# ioboard.net
KiCad netlist of a schematic drawn in EAGLE
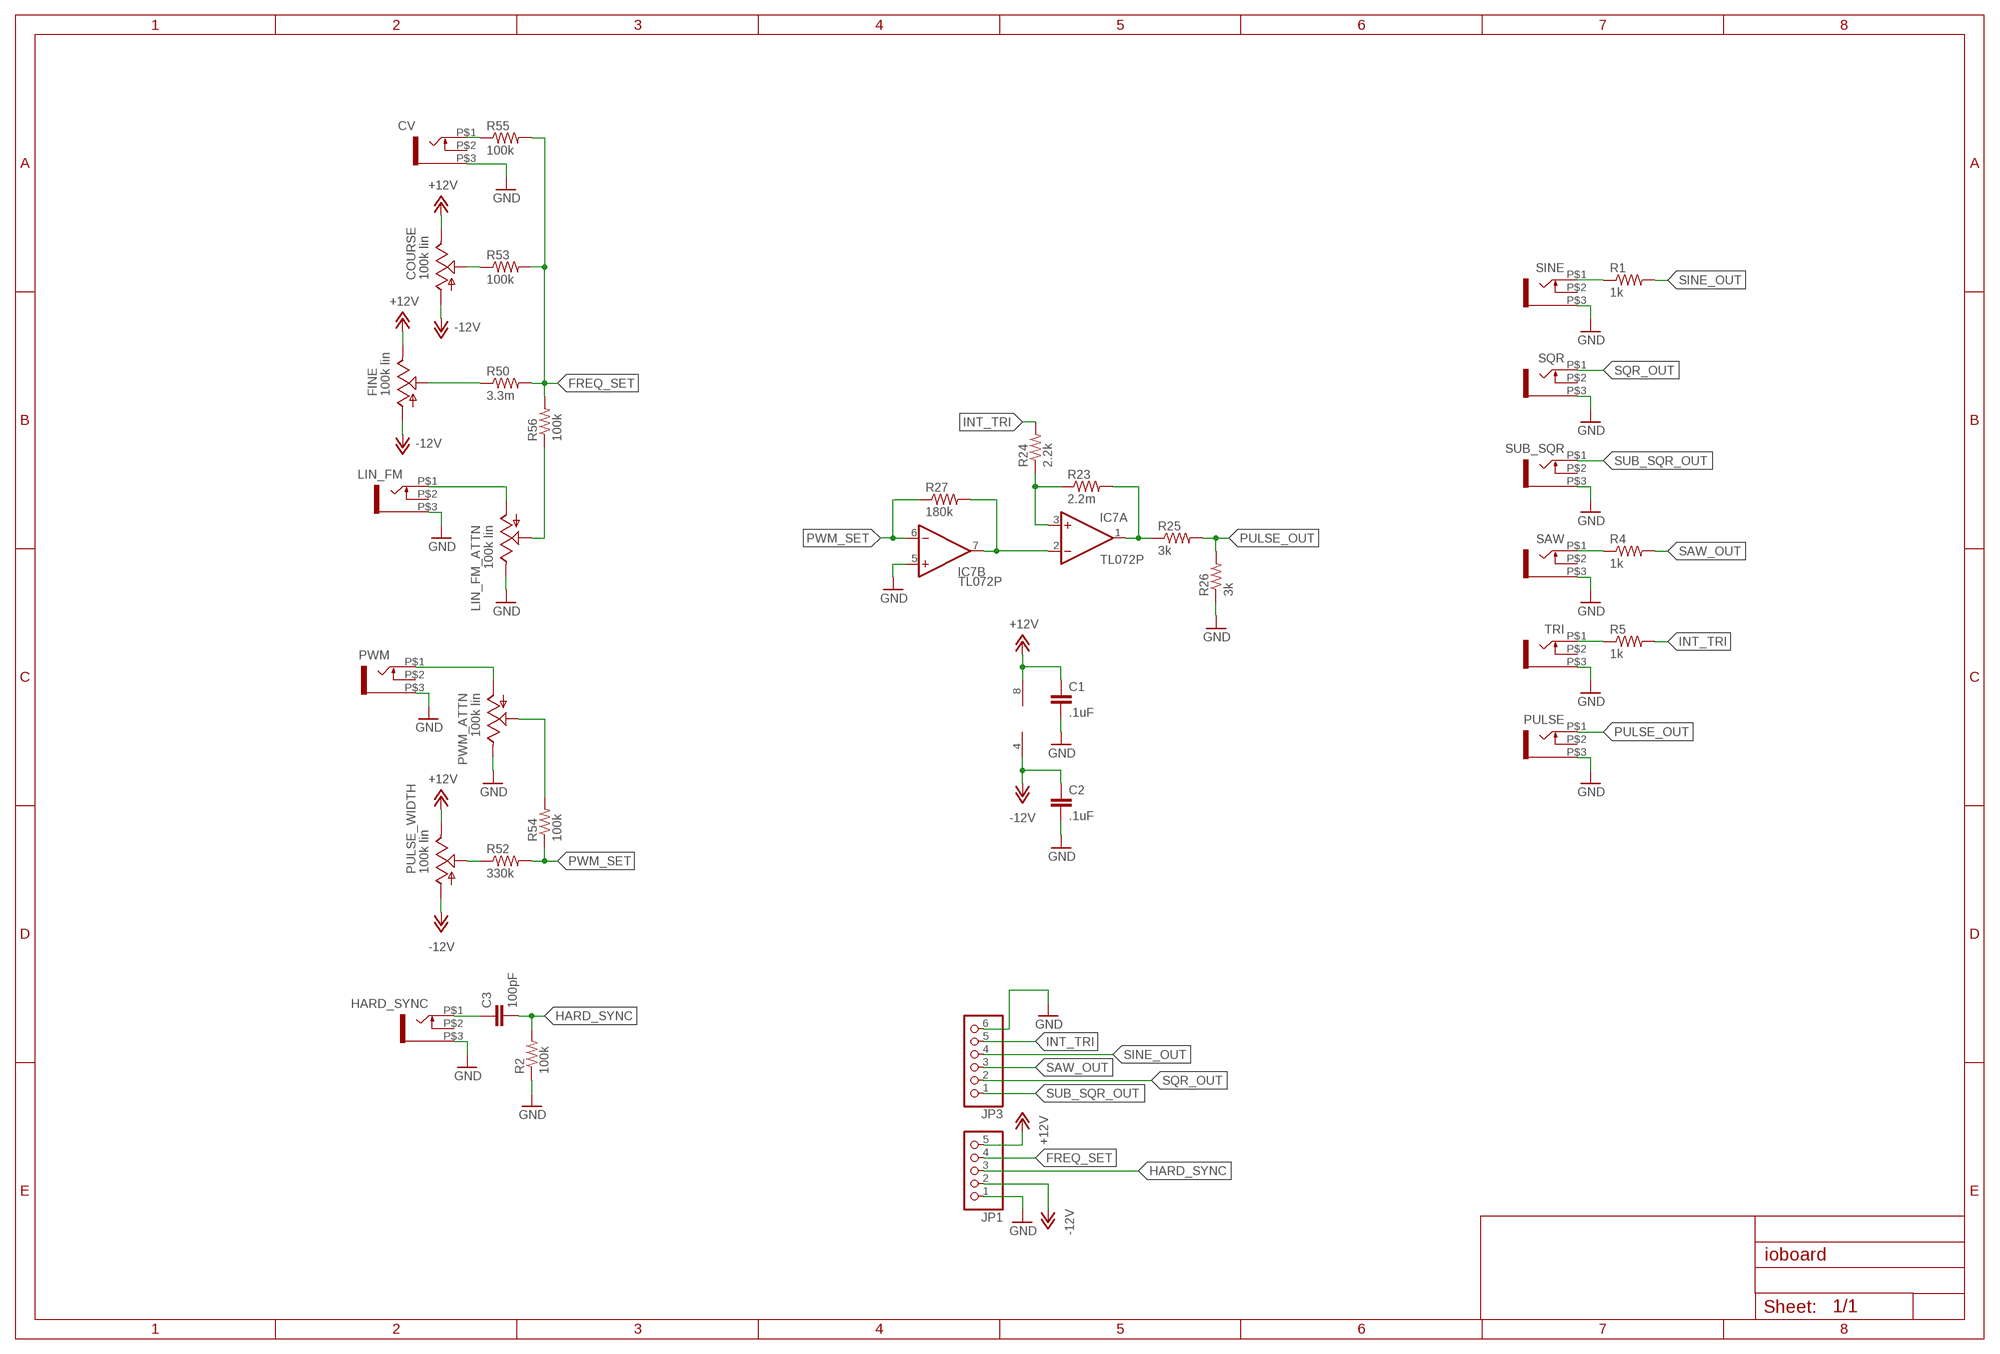
[diagram p0: schematic, sheet 1]

(export (version "E")
  (design (tool "Eeschema 10.0.6"))
  (components
    (comp (ref "C1")
      (value ".1uF")
      (footprint "eagle-import:C050-024X044")
      (libsource (lib "eagle-import") (part "C-EU050-024X044"))
    )
    (comp (ref "C2")
      (value ".1uF")
      (footprint "eagle-import:C050-024X044")
      (libsource (lib "eagle-import") (part "C-EU050-024X044"))
    )
    (comp (ref "C3")
      (value "100pF")
      (footprint "eagle-import:C050-024X044")
      (libsource (lib "eagle-import") (part "C-EU050-024X044"))
    )
    (comp (ref "COURSE")
      (value "100k lin")
      (footprint "eagle-import:EVUF")
      (libsource (lib "eagle-import") (part "ALPHA-9MMA"))
    )
    (comp (ref "CV")
      (value "WQP-PJ301M-12_JACK")
      (footprint "eagle-import:WQP-PJ301M-12_JACK")
      (libsource (lib "eagle-import") (part "WQP-PJ301M-12_JACK"))
    )
    (comp (ref "FINE")
      (value "100k lin")
      (footprint "eagle-import:EVUF")
      (libsource (lib "eagle-import") (part "ALPHA-9MMA"))
    )
    (comp (ref "HARD_SYNC")
      (value "WQP-PJ301M-12_JACK")
      (footprint "eagle-import:WQP-PJ301M-12_JACK")
      (libsource (lib "eagle-import") (part "WQP-PJ301M-12_JACK"))
    )
    (comp (ref "IC7")
      (value "TL072P")
      (footprint "eagle-import:DIL08")
      (libsource (lib "eagle-import") (part "TL072P"))
    )
    (comp (ref "JP1")
      (value "PINHD-1X5")
      (footprint "eagle-import:1X05")
      (libsource (lib "eagle-import") (part "PINHD-1X5"))
    )
    (comp (ref "JP3")
      (value "PINHD-1X6")
      (footprint "eagle-import:1X06")
      (libsource (lib "eagle-import") (part "PINHD-1X6"))
    )
    (comp (ref "LIN_FM")
      (value "WQP-PJ301M-12_JACK")
      (footprint "eagle-import:WQP-PJ301M-12_JACK")
      (libsource (lib "eagle-import") (part "WQP-PJ301M-12_JACK"))
    )
    (comp (ref "LIN_FM_ATTN")
      (value "100k lin")
      (footprint "eagle-import:EVUF")
      (libsource (lib "eagle-import") (part "ALPHA-9MMA"))
    )
    (comp (ref "PULSE")
      (value "WQP-PJ301M-12_JACK")
      (footprint "eagle-import:WQP-PJ301M-12_JACK")
      (libsource (lib "eagle-import") (part "WQP-PJ301M-12_JACK"))
    )
    (comp (ref "PULSE_WIDTH")
      (value "100k lin")
      (footprint "eagle-import:EVUF")
      (libsource (lib "eagle-import") (part "ALPHA-9MMA"))
    )
    (comp (ref "PWM")
      (value "WQP-PJ301M-12_JACK")
      (footprint "eagle-import:WQP-PJ301M-12_JACK")
      (libsource (lib "eagle-import") (part "WQP-PJ301M-12_JACK"))
    )
    (comp (ref "PWM_ATTN")
      (value "100k lin")
      (footprint "eagle-import:EVUF")
      (libsource (lib "eagle-import") (part "ALPHA-9MMA"))
    )
    (comp (ref "R1")
      (value "1k")
      (footprint "eagle-import:0204_7")
      (libsource (lib "eagle-import") (part "R-US_0204/7"))
    )
    (comp (ref "R2")
      (value "100k")
      (footprint "eagle-import:0204_7")
      (libsource (lib "eagle-import") (part "R-US_0204/7"))
    )
    (comp (ref "R4")
      (value "1k")
      (footprint "eagle-import:0204_7")
      (libsource (lib "eagle-import") (part "R-US_0204/7"))
    )
    (comp (ref "R5")
      (value "1k")
      (footprint "eagle-import:0204_7")
      (libsource (lib "eagle-import") (part "R-US_0204/7"))
    )
    (comp (ref "R23")
      (value "2.2m")
      (footprint "eagle-import:0204_7")
      (libsource (lib "eagle-import") (part "R-US_0204/7"))
    )
    (comp (ref "R24")
      (value "2.2k")
      (footprint "eagle-import:0204_7")
      (libsource (lib "eagle-import") (part "R-US_0204/7"))
    )
    (comp (ref "R25")
      (value "3k")
      (footprint "eagle-import:0204_7")
      (libsource (lib "eagle-import") (part "R-US_0204/7"))
    )
    (comp (ref "R26")
      (value "3k")
      (footprint "eagle-import:0204_7")
      (libsource (lib "eagle-import") (part "R-US_0204/7"))
    )
    (comp (ref "R27")
      (value "180k")
      (footprint "eagle-import:0204_7")
      (libsource (lib "eagle-import") (part "R-US_0204/7"))
    )
    (comp (ref "R50")
      (value "3.3m")
      (footprint "eagle-import:0204_7")
      (libsource (lib "eagle-import") (part "R-US_0204/7"))
    )
    (comp (ref "R52")
      (value "330k")
      (footprint "eagle-import:0204_7")
      (libsource (lib "eagle-import") (part "R-US_0204/7"))
    )
    (comp (ref "R53")
      (value "100k")
      (footprint "eagle-import:0204_7")
      (libsource (lib "eagle-import") (part "R-US_0204/7"))
    )
    (comp (ref "R54")
      (value "100k")
      (footprint "eagle-import:0204_7")
      (libsource (lib "eagle-import") (part "R-US_0204/7"))
    )
    (comp (ref "R55")
      (value "100k")
      (footprint "eagle-import:0204_7")
      (libsource (lib "eagle-import") (part "R-US_0204/7"))
    )
    (comp (ref "R56")
      (value "100k")
      (footprint "eagle-import:0204_7")
      (libsource (lib "eagle-import") (part "R-US_0204/7"))
    )
    (comp (ref "SAW")
      (value "WQP-PJ301M-12_JACK")
      (footprint "eagle-import:WQP-PJ301M-12_JACK")
      (libsource (lib "eagle-import") (part "WQP-PJ301M-12_JACK"))
    )
    (comp (ref "SINE")
      (value "WQP-PJ301M-12_JACK")
      (footprint "eagle-import:WQP-PJ301M-12_JACK")
      (libsource (lib "eagle-import") (part "WQP-PJ301M-12_JACK"))
    )
    (comp (ref "SQR")
      (value "WQP-PJ301M-12_JACK")
      (footprint "eagle-import:WQP-PJ301M-12_JACK")
      (libsource (lib "eagle-import") (part "WQP-PJ301M-12_JACK"))
    )
    (comp (ref "SUB_SQR")
      (value "WQP-PJ301M-12_JACK")
      (footprint "eagle-import:WQP-PJ301M-12_JACK")
      (libsource (lib "eagle-import") (part "WQP-PJ301M-12_JACK"))
    )
    (comp (ref "TRI")
      (value "WQP-PJ301M-12_JACK")
      (footprint "eagle-import:WQP-PJ301M-12_JACK")
      (libsource (lib "eagle-import") (part "WQP-PJ301M-12_JACK"))
    )
  )
  (nets
    (net (code "1") (name "+12V") (class "Default")
      (node (ref "C1") (pin "1") (pinfunction "1_1") (pintype "passive"))
      (node (ref "COURSE") (pin "3") (pinfunction "E_3") (pintype "passive"))
      (node (ref "FINE") (pin "3") (pinfunction "E_3") (pintype "passive"))
      (node (ref "IC7") (pin "8") (pinfunction "V+_8") (pintype "power_in"))
      (node (ref "JP1") (pin "5") (pinfunction "5_5") (pintype "passive"))
      (node (ref "PULSE_WIDTH") (pin "3") (pinfunction "E_3") (pintype "passive"))
    )
    (net (code "2") (name "-12V") (class "Default")
      (node (ref "C2") (pin "1") (pinfunction "1_1") (pintype "passive"))
      (node (ref "COURSE") (pin "1") (pinfunction "A_1") (pintype "passive"))
      (node (ref "FINE") (pin "1") (pinfunction "A_1") (pintype "passive"))
      (node (ref "IC7") (pin "4") (pinfunction "V-_4") (pintype "power_in"))
      (node (ref "JP1") (pin "2") (pinfunction "2_2") (pintype "passive"))
      (node (ref "PULSE_WIDTH") (pin "1") (pinfunction "A_1") (pintype "passive"))
    )
    (net (code "3") (name "FREQ_SET") (class "Default")
      (node (ref "JP1") (pin "4") (pinfunction "4_4") (pintype "passive"))
      (node (ref "R50") (pin "2") (pinfunction "2_2") (pintype "passive"))
      (node (ref "R53") (pin "2") (pinfunction "2_2") (pintype "passive"))
      (node (ref "R55") (pin "2") (pinfunction "2_2") (pintype "passive"))
      (node (ref "R56") (pin "2") (pinfunction "2_2") (pintype "passive"))
    )
    (net (code "4") (name "GND") (class "Default")
      (node (ref "C1") (pin "2") (pinfunction "2_2") (pintype "passive"))
      (node (ref "C2") (pin "2") (pinfunction "2_2") (pintype "passive"))
      (node (ref "CV") (pin "P$3") (pinfunction "1_P$3") (pintype "passive"))
      (node (ref "HARD_SYNC") (pin "P$3") (pinfunction "1_P$3") (pintype "passive"))
      (node (ref "IC7") (pin "5") (pinfunction "+IN_5") (pintype "input"))
      (node (ref "JP1") (pin "1") (pinfunction "1_1") (pintype "passive"))
      (node (ref "JP3") (pin "6") (pinfunction "6_6") (pintype "passive"))
      (node (ref "LIN_FM") (pin "P$3") (pinfunction "1_P$3") (pintype "passive"))
      (node (ref "LIN_FM_ATTN") (pin "3") (pinfunction "E_3") (pintype "passive"))
      (node (ref "PULSE") (pin "P$3") (pinfunction "1_P$3") (pintype "passive"))
      (node (ref "PWM") (pin "P$3") (pinfunction "1_P$3") (pintype "passive"))
      (node (ref "PWM_ATTN") (pin "3") (pinfunction "E_3") (pintype "passive"))
      (node (ref "R2") (pin "1") (pinfunction "1_1") (pintype "passive"))
      (node (ref "R26") (pin "1") (pinfunction "1_1") (pintype "passive"))
      (node (ref "SAW") (pin "P$3") (pinfunction "1_P$3") (pintype "passive"))
      (node (ref "SINE") (pin "P$3") (pinfunction "1_P$3") (pintype "passive"))
      (node (ref "SQR") (pin "P$3") (pinfunction "1_P$3") (pintype "passive"))
      (node (ref "SUB_SQR") (pin "P$3") (pinfunction "1_P$3") (pintype "passive"))
      (node (ref "TRI") (pin "P$3") (pinfunction "1_P$3") (pintype "passive"))
    )
    (net (code "5") (name "HARD_SYNC") (class "Default")
      (node (ref "C3") (pin "2") (pinfunction "2_2") (pintype "passive"))
      (node (ref "JP1") (pin "3") (pinfunction "3_3") (pintype "passive"))
      (node (ref "R2") (pin "2") (pinfunction "2_2") (pintype "passive"))
    )
    (net (code "6") (name "INT_TRI") (class "Default")
      (node (ref "JP3") (pin "5") (pinfunction "5_5") (pintype "passive"))
      (node (ref "R24") (pin "2") (pinfunction "2_2") (pintype "passive"))
      (node (ref "R5") (pin "2") (pinfunction "2_2") (pintype "passive"))
    )
    (net (code "7") (name "Net-(COURSE-S)") (class "Default")
      (node (ref "COURSE") (pin "2") (pinfunction "S_2") (pintype "passive"))
      (node (ref "R53") (pin "1") (pinfunction "1_1") (pintype "passive"))
    )
    (net (code "8") (name "Net-(CV-2)") (class "Default")
      (node (ref "CV") (pin "P$1") (pinfunction "2_P$1") (pintype "passive"))
      (node (ref "R55") (pin "1") (pinfunction "1_1") (pintype "passive"))
    )
    (net (code "9") (name "Net-(FINE-S)") (class "Default")
      (node (ref "FINE") (pin "2") (pinfunction "S_2") (pintype "passive"))
      (node (ref "R50") (pin "1") (pinfunction "1_1") (pintype "passive"))
    )
    (net (code "10") (name "Net-(HARD_SYNC-2)") (class "Default")
      (node (ref "C3") (pin "1") (pinfunction "1_1") (pintype "passive"))
      (node (ref "HARD_SYNC") (pin "P$1") (pinfunction "2_P$1") (pintype "passive"))
    )
    (net (code "11") (name "Net-(IC7A-+IN)") (class "Default")
      (node (ref "IC7") (pin "3") (pinfunction "+IN_3") (pintype "input"))
      (node (ref "R23") (pin "1") (pinfunction "1_1") (pintype "passive"))
      (node (ref "R24") (pin "1") (pinfunction "1_1") (pintype "passive"))
    )
    (net (code "12") (name "Net-(IC7A--IN)") (class "Default")
      (node (ref "IC7") (pin "2") (pinfunction "-IN_2") (pintype "input"))
      (node (ref "IC7") (pin "7") (pinfunction "OUT_7") (pintype "output"))
      (node (ref "R27") (pin "2") (pinfunction "2_2") (pintype "passive"))
    )
    (net (code "13") (name "Net-(IC7A-OUT)") (class "Default")
      (node (ref "IC7") (pin "1") (pinfunction "OUT_1") (pintype "output"))
      (node (ref "R23") (pin "2") (pinfunction "2_2") (pintype "passive"))
      (node (ref "R25") (pin "1") (pinfunction "1_1") (pintype "passive"))
    )
    (net (code "14") (name "Net-(LIN_FM-2)") (class "Default")
      (node (ref "LIN_FM") (pin "P$1") (pinfunction "2_P$1") (pintype "passive"))
      (node (ref "LIN_FM_ATTN") (pin "1") (pinfunction "A_1") (pintype "passive"))
    )
    (net (code "15") (name "Net-(LIN_FM_ATTN-S)") (class "Default")
      (node (ref "LIN_FM_ATTN") (pin "2") (pinfunction "S_2") (pintype "passive"))
      (node (ref "R56") (pin "1") (pinfunction "1_1") (pintype "passive"))
    )
    (net (code "16") (name "Net-(PULSE_WIDTH-S)") (class "Default")
      (node (ref "PULSE_WIDTH") (pin "2") (pinfunction "S_2") (pintype "passive"))
      (node (ref "R52") (pin "1") (pinfunction "1_1") (pintype "passive"))
    )
    (net (code "17") (name "Net-(PWM-2)") (class "Default")
      (node (ref "PWM") (pin "P$1") (pinfunction "2_P$1") (pintype "passive"))
      (node (ref "PWM_ATTN") (pin "1") (pinfunction "A_1") (pintype "passive"))
    )
    (net (code "18") (name "Net-(PWM_ATTN-S)") (class "Default")
      (node (ref "PWM_ATTN") (pin "2") (pinfunction "S_2") (pintype "passive"))
      (node (ref "R54") (pin "2") (pinfunction "2_2") (pintype "passive"))
    )
    (net (code "19") (name "Net-(SAW-2)") (class "Default")
      (node (ref "R4") (pin "1") (pinfunction "1_1") (pintype "passive"))
      (node (ref "SAW") (pin "P$1") (pinfunction "2_P$1") (pintype "passive"))
    )
    (net (code "20") (name "Net-(SINE-2)") (class "Default")
      (node (ref "R1") (pin "1") (pinfunction "1_1") (pintype "passive"))
      (node (ref "SINE") (pin "P$1") (pinfunction "2_P$1") (pintype "passive"))
    )
    (net (code "21") (name "Net-(TRI-2)") (class "Default")
      (node (ref "R5") (pin "1") (pinfunction "1_1") (pintype "passive"))
      (node (ref "TRI") (pin "P$1") (pinfunction "2_P$1") (pintype "passive"))
    )
    (net (code "22") (name "PULSE_OUT") (class "Default")
      (node (ref "PULSE") (pin "P$1") (pinfunction "2_P$1") (pintype "passive"))
      (node (ref "R25") (pin "2") (pinfunction "2_2") (pintype "passive"))
      (node (ref "R26") (pin "2") (pinfunction "2_2") (pintype "passive"))
    )
    (net (code "23") (name "PWM_SET") (class "Default")
      (node (ref "IC7") (pin "6") (pinfunction "-IN_6") (pintype "input"))
      (node (ref "R27") (pin "1") (pinfunction "1_1") (pintype "passive"))
      (node (ref "R52") (pin "2") (pinfunction "2_2") (pintype "passive"))
      (node (ref "R54") (pin "1") (pinfunction "1_1") (pintype "passive"))
    )
    (net (code "24") (name "SAW_OUT") (class "Default")
      (node (ref "JP3") (pin "3") (pinfunction "3_3") (pintype "passive"))
      (node (ref "R4") (pin "2") (pinfunction "2_2") (pintype "passive"))
    )
    (net (code "25") (name "SINE_OUT") (class "Default")
      (node (ref "JP3") (pin "4") (pinfunction "4_4") (pintype "passive"))
      (node (ref "R1") (pin "2") (pinfunction "2_2") (pintype "passive"))
    )
    (net (code "26") (name "SQR_OUT") (class "Default")
      (node (ref "JP3") (pin "2") (pinfunction "2_2") (pintype "passive"))
      (node (ref "SQR") (pin "P$1") (pinfunction "2_P$1") (pintype "passive"))
    )
    (net (code "27") (name "SUB_SQR_OUT") (class "Default")
      (node (ref "JP3") (pin "1") (pinfunction "1_1") (pintype "passive"))
      (node (ref "SUB_SQR") (pin "P$1") (pinfunction "2_P$1") (pintype "passive"))
    )
    (net (code "28") (name "unconnected-(CV-3-PadP$2)") (class "Default")
      (node (ref "CV") (pin "P$2") (pinfunction "3_P$2") (pintype "passive"))
    )
    (net (code "29") (name "unconnected-(HARD_SYNC-3-PadP$2)") (class "Default")
      (node (ref "HARD_SYNC") (pin "P$2") (pinfunction "3_P$2") (pintype "passive"))
    )
    (net (code "30") (name "unconnected-(LIN_FM-3-PadP$2)") (class "Default")
      (node (ref "LIN_FM") (pin "P$2") (pinfunction "3_P$2") (pintype "passive"))
    )
    (net (code "31") (name "unconnected-(PULSE-3-PadP$2)") (class "Default")
      (node (ref "PULSE") (pin "P$2") (pinfunction "3_P$2") (pintype "passive"))
    )
    (net (code "32") (name "unconnected-(PWM-3-PadP$2)") (class "Default")
      (node (ref "PWM") (pin "P$2") (pinfunction "3_P$2") (pintype "passive"))
    )
    (net (code "33") (name "unconnected-(SAW-3-PadP$2)") (class "Default")
      (node (ref "SAW") (pin "P$2") (pinfunction "3_P$2") (pintype "passive"))
    )
    (net (code "34") (name "unconnected-(SINE-3-PadP$2)") (class "Default")
      (node (ref "SINE") (pin "P$2") (pinfunction "3_P$2") (pintype "passive"))
    )
    (net (code "35") (name "unconnected-(SQR-3-PadP$2)") (class "Default")
      (node (ref "SQR") (pin "P$2") (pinfunction "3_P$2") (pintype "passive"))
    )
    (net (code "36") (name "unconnected-(SUB_SQR-3-PadP$2)") (class "Default")
      (node (ref "SUB_SQR") (pin "P$2") (pinfunction "3_P$2") (pintype "passive"))
    )
    (net (code "37") (name "unconnected-(TRI-3-PadP$2)") (class "Default")
      (node (ref "TRI") (pin "P$2") (pinfunction "3_P$2") (pintype "passive"))
    )
  )
)
